# io-board-a-4.net
KiCad netlist of a schematic drawn in EAGLE
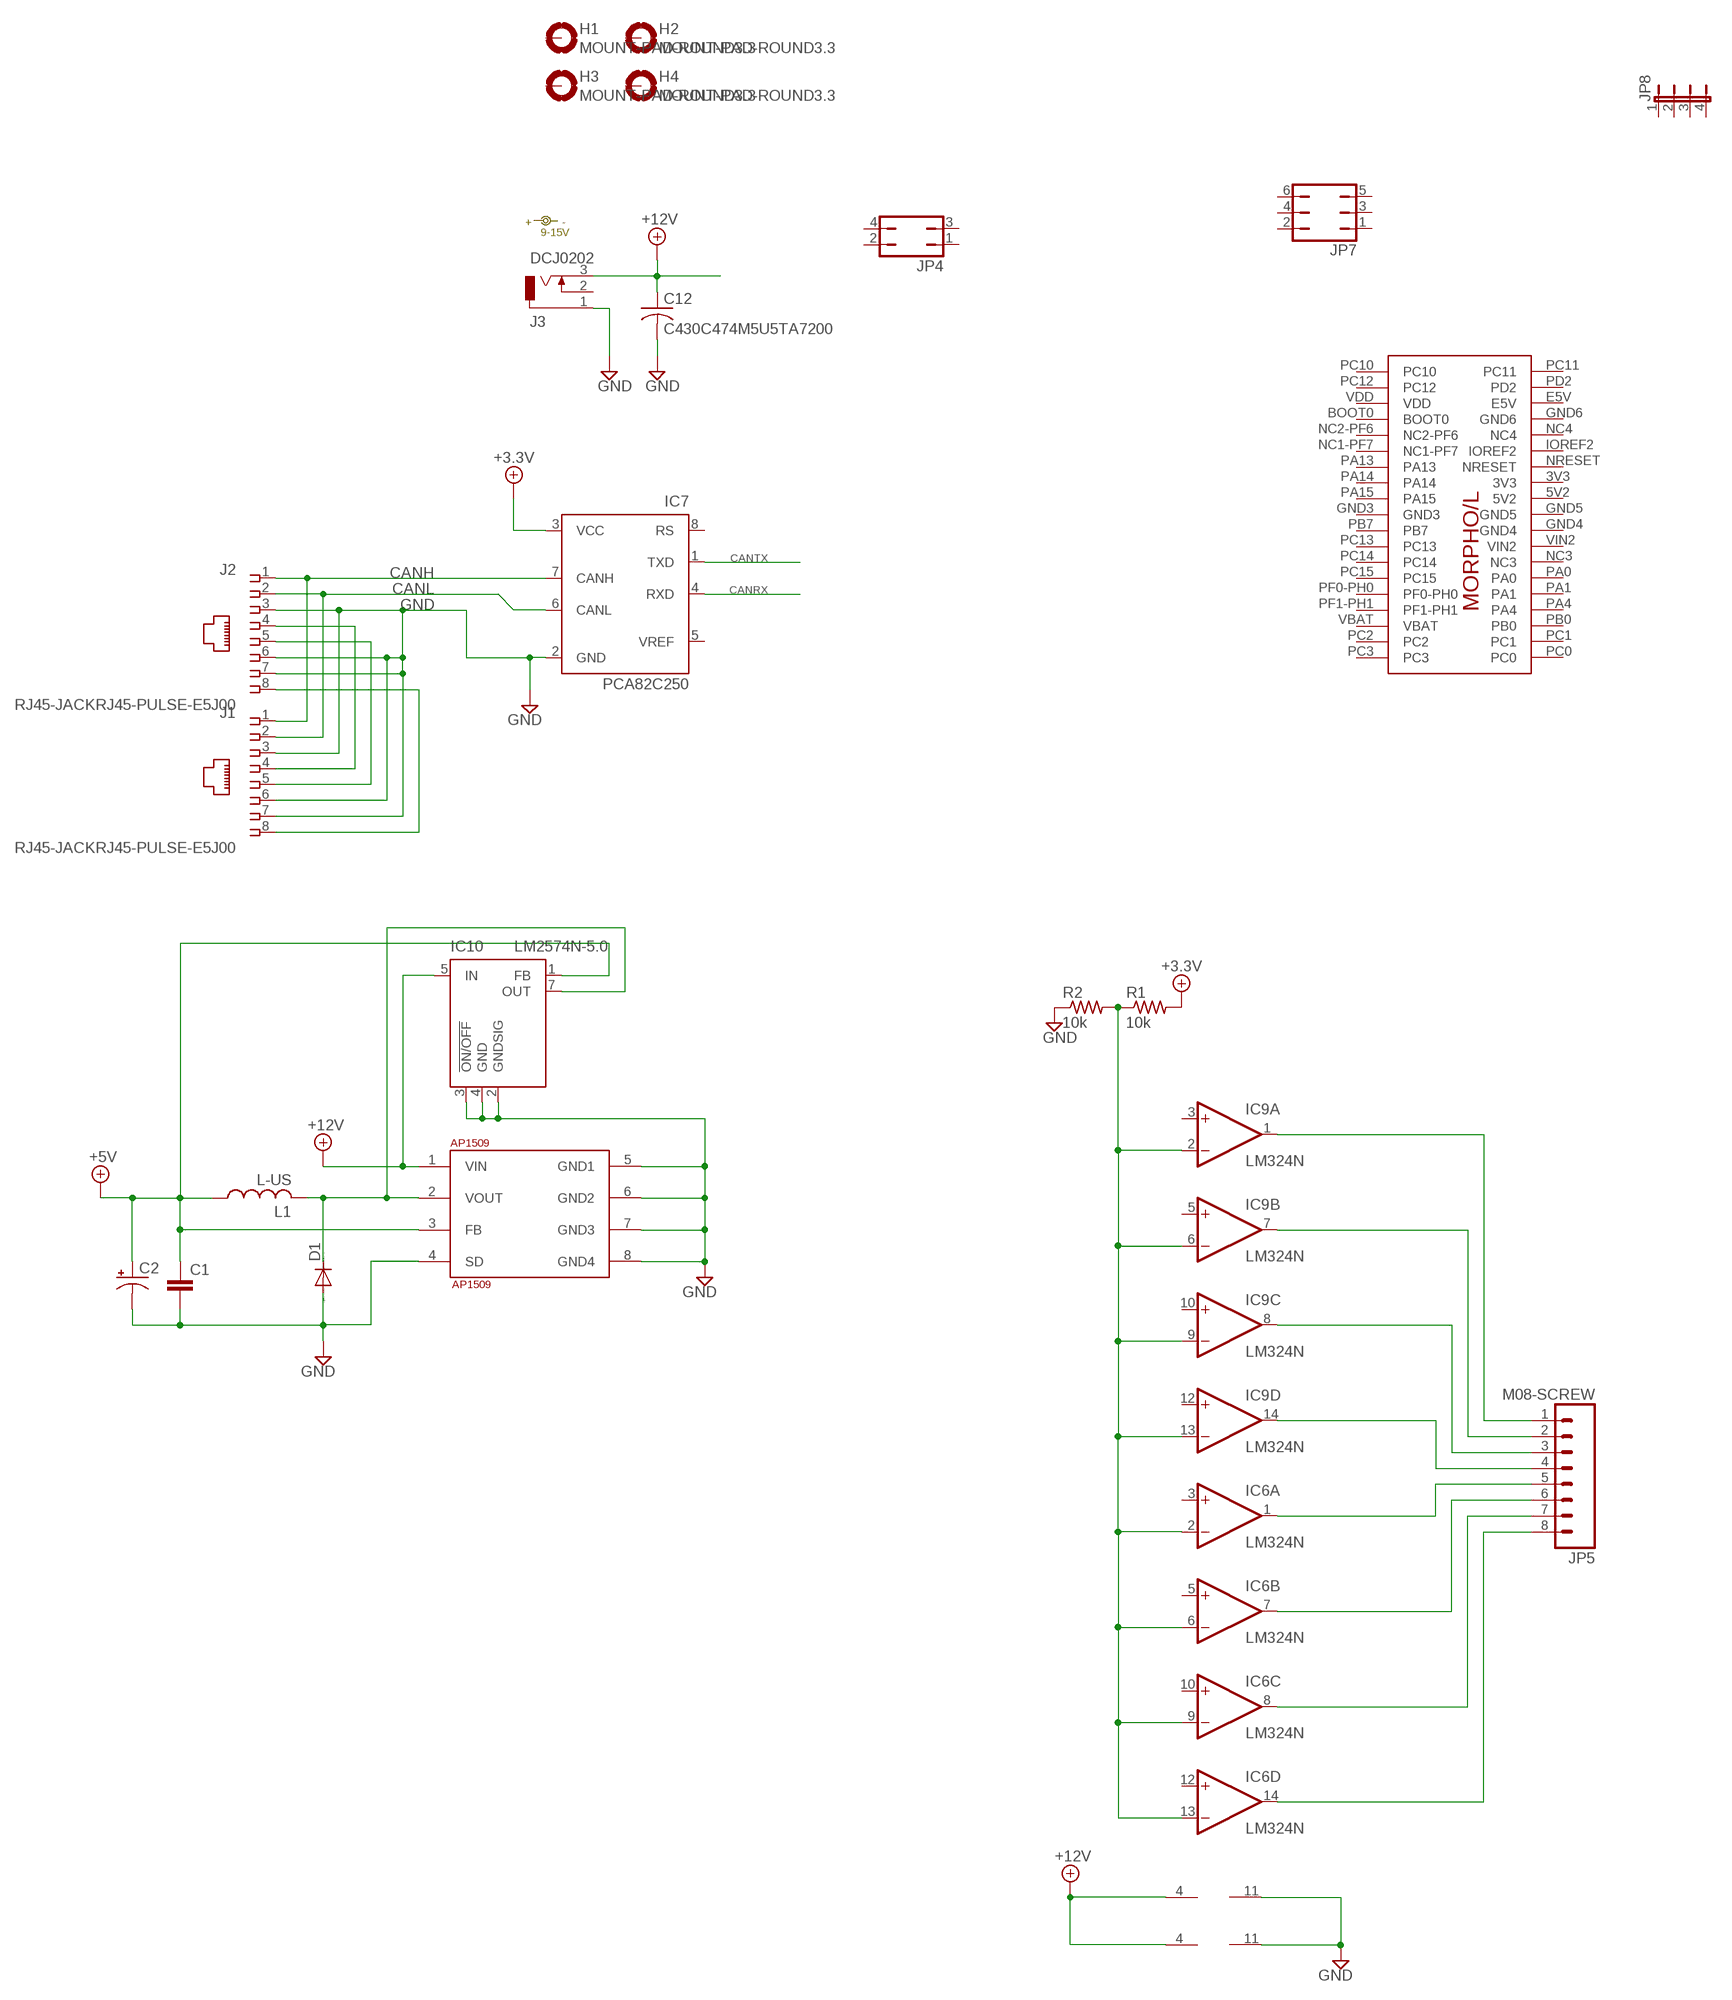
[diagram p0: schematic, sheet 1, part 1 of 2]
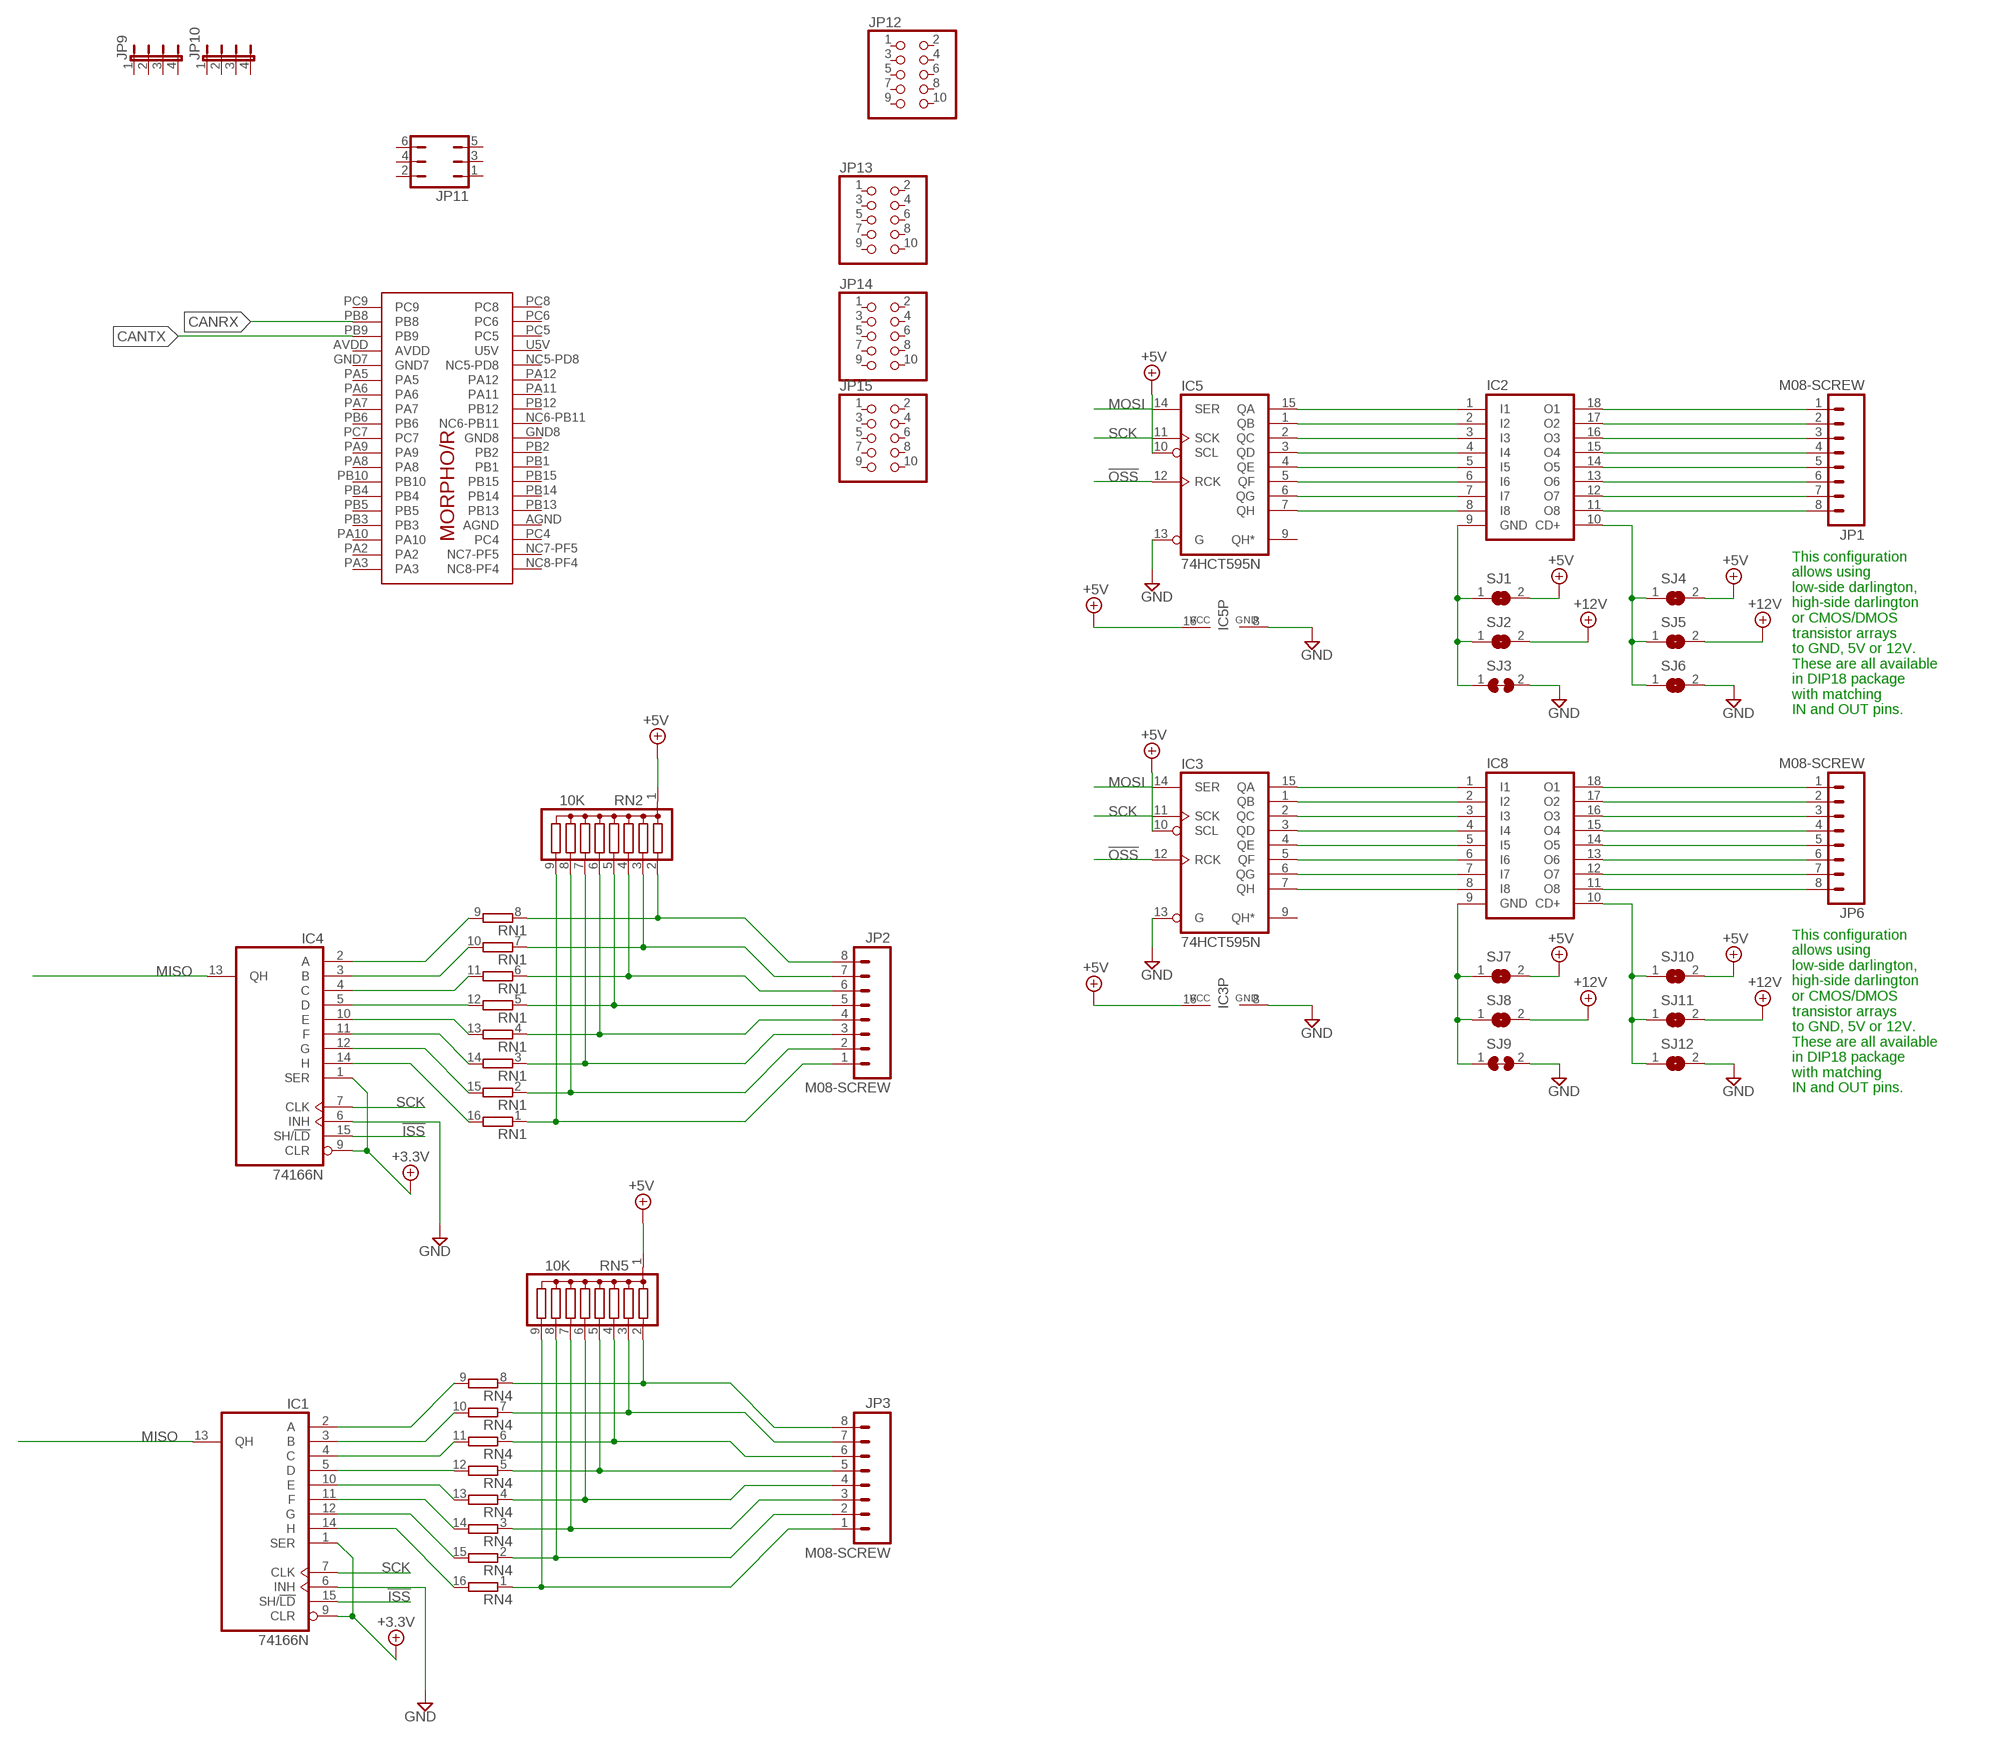
[diagram p1: schematic, sheet 1, part 2 of 2]

(export (version "E")
  (design (tool "Eeschema 10.0.6"))
  (components
    (comp (ref "+12V")
      (value "9-15V")
      (footprint "eagle-import:POWER_USAGE")
      (libsource (lib "eagle-import") (part "DOC-POWER_LABEL"))
    )
    (comp (ref "AP1509")
      (value "AP1509")
      (footprint "eagle-import:SO-08")
      (libsource (lib "eagle-import") (part "AP1509"))
    )
    (comp (ref "C1")
      (value "C-EUC1206")
      (footprint "eagle-import:C1206")
      (libsource (lib "eagle-import") (part "C-EUC1206"))
    )
    (comp (ref "C2")
      (value "CPOL-USE2.5-5")
      (footprint "eagle-import:E2,5-5")
      (libsource (lib "eagle-import") (part "CPOL-USE2.5-5"))
    )
    (comp (ref "C12")
      (value "C430C474M5U5TA7200")
      (footprint "eagle-import:C075-032X103")
      (libsource (lib "eagle-import") (part "C-US075-032X103"))
    )
    (comp (ref "D1")
      (value "DIODE-DO41-7.6")
      (footprint "eagle-import:DO41-7.6")
      (libsource (lib "eagle-import") (part "DIODE-DO41-7.6"))
    )
    (comp (ref "H1")
      (value "MOUNT-PAD-ROUND3.3")
      (footprint "eagle-import:3,3-PAD")
      (libsource (lib "eagle-import") (part "MOUNT-PAD-ROUND3.3"))
    )
    (comp (ref "H2")
      (value "MOUNT-PAD-ROUND3.3")
      (footprint "eagle-import:3,3-PAD")
      (libsource (lib "eagle-import") (part "MOUNT-PAD-ROUND3.3"))
    )
    (comp (ref "H3")
      (value "MOUNT-PAD-ROUND3.3")
      (footprint "eagle-import:3,3-PAD")
      (libsource (lib "eagle-import") (part "MOUNT-PAD-ROUND3.3"))
    )
    (comp (ref "H4")
      (value "MOUNT-PAD-ROUND3.3")
      (footprint "eagle-import:3,3-PAD")
      (libsource (lib "eagle-import") (part "MOUNT-PAD-ROUND3.3"))
    )
    (comp (ref "IC1")
      (value "74166N")
      (footprint "eagle-import:DIL16")
      (libsource (lib "eagle-import") (part "74166N"))
    )
    (comp (ref "IC2")
      (value "ULN2803A")
      (footprint "eagle-import:DIL18")
      (libsource (lib "eagle-import") (part "ULN2803A"))
    )
    (comp (ref "IC3")
      (value "74HCT595N")
      (footprint "eagle-import:DIL16")
      (libsource (lib "eagle-import") (part "74595NHCT"))
    )
    (comp (ref "IC4")
      (value "74166N")
      (footprint "eagle-import:DIL16")
      (libsource (lib "eagle-import") (part "74166N"))
    )
    (comp (ref "IC5")
      (value "74HCT595N")
      (footprint "eagle-import:DIL16")
      (libsource (lib "eagle-import") (part "74595NHCT"))
    )
    (comp (ref "IC6")
      (value "LM324N")
      (footprint "eagle-import:DIL14")
      (libsource (lib "eagle-import") (part "LM324N"))
    )
    (comp (ref "IC7")
      (value "PCA82C250")
      (footprint "eagle-import:DIL08")
      (libsource (lib "eagle-import") (part "PCA82C250"))
    )
    (comp (ref "IC8")
      (value "ULN2803A")
      (footprint "eagle-import:DIL18")
      (libsource (lib "eagle-import") (part "ULN2803A"))
    )
    (comp (ref "IC9")
      (value "LM324N")
      (footprint "eagle-import:DIL14")
      (libsource (lib "eagle-import") (part "LM324N"))
    )
    (comp (ref "IC10")
      (value "LM2574N-5.0")
      (footprint "eagle-import:DIL08")
      (libsource (lib "eagle-import") (part "LM2574?-N5.0"))
    )
    (comp (ref "J1")
      (value "RJ45-JACKRJ45-PULSE-E5J00")
      (footprint "eagle-import:RJ45-PULSE-E5J88")
      (libsource (lib "eagle-import") (part "RJ45-JACKRJ45-PULSE-E5J00"))
    )
    (comp (ref "J2")
      (value "RJ45-JACKRJ45-PULSE-E5J00")
      (footprint "eagle-import:RJ45-PULSE-E5J88")
      (libsource (lib "eagle-import") (part "RJ45-JACKRJ45-PULSE-E5J00"))
    )
    (comp (ref "J3")
      (value "DCJ0202")
      (footprint "eagle-import:DCJ0202")
      (libsource (lib "eagle-import") (part "DCJ0202"))
    )
    (comp (ref "JP1")
      (value "M08-SCREW")
      (footprint "eagle-import:1X08_TERMINAL")
      (libsource (lib "eagle-import") (part "M08-SCREW"))
    )
    (comp (ref "JP2")
      (value "M08-SCREW")
      (footprint "eagle-import:1X08_TERMINAL")
      (libsource (lib "eagle-import") (part "M08-SCREW"))
    )
    (comp (ref "JP3")
      (value "M08-SCREW")
      (footprint "eagle-import:1X08_TERMINAL")
      (libsource (lib "eagle-import") (part "M08-SCREW"))
    )
    (comp (ref "JP4")
      (value "JP2Q")
      (footprint "eagle-import:JP2Q")
      (libsource (lib "eagle-import") (part "JP2Q"))
    )
    (comp (ref "JP5")
      (value "M08-SCREW")
      (footprint "eagle-import:1X08_TERMINAL")
      (libsource (lib "eagle-import") (part "M08-SCREW"))
    )
    (comp (ref "JP6")
      (value "M08-SCREW")
      (footprint "eagle-import:1X08_TERMINAL")
      (libsource (lib "eagle-import") (part "M08-SCREW"))
    )
    (comp (ref "JP7")
      (value "JP3Q")
      (footprint "eagle-import:JP3Q")
      (libsource (lib "eagle-import") (part "JP3Q"))
    )
    (comp (ref "JP8")
      (value "JP4-FLAT")
      (footprint "eagle-import:JP4F")
      (libsource (lib "eagle-import") (part "JP4-FLAT"))
    )
    (comp (ref "JP9")
      (value "JP4-FLAT")
      (footprint "eagle-import:JP4F")
      (libsource (lib "eagle-import") (part "JP4-FLAT"))
    )
    (comp (ref "JP10")
      (value "JP4-FLAT")
      (footprint "eagle-import:JP4F")
      (libsource (lib "eagle-import") (part "JP4-FLAT"))
    )
    (comp (ref "JP11")
      (value "JP3Q")
      (footprint "eagle-import:JP3Q")
      (libsource (lib "eagle-import") (part "JP3Q"))
    )
    (comp (ref "JP12")
      (value "PINHD-2X5")
      (footprint "eagle-import:2X05")
      (libsource (lib "eagle-import") (part "PINHD-2X5"))
    )
    (comp (ref "JP13")
      (value "PINHD-2X5CN")
      (footprint "eagle-import:CON10M")
      (libsource (lib "eagle-import") (part "PINHD-2X5CN"))
    )
    (comp (ref "JP14")
      (value "PINHD-2X5CN")
      (footprint "eagle-import:CON10M")
      (libsource (lib "eagle-import") (part "PINHD-2X5CN"))
    )
    (comp (ref "JP15")
      (value "PINHD-2X5CN")
      (footprint "eagle-import:CON10M")
      (libsource (lib "eagle-import") (part "PINHD-2X5CN"))
    )
    (comp (ref "L1")
      (value "L-US")
      (footprint "eagle-import:L5-8,5")
      (libsource (lib "eagle-import") (part "L-US"))
    )
    (comp (ref "R1")
      (value "10k")
      (footprint "eagle-import:R1206")
      (libsource (lib "eagle-import") (part "R-US_R1206"))
    )
    (comp (ref "R2")
      (value "10k")
      (footprint "eagle-import:R1206")
      (libsource (lib "eagle-import") (part "R-US_R1206"))
    )
    (comp (ref "RN1")
      (value "8R-P")
      (footprint "eagle-import:DIL16")
      (libsource (lib "eagle-import") (part "8R-P"))
    )
    (comp (ref "RN2")
      (value "10K")
      (footprint "eagle-import:SIL9")
      (libsource (lib "eagle-import") (part "G08R"))
    )
    (comp (ref "RN4")
      (value "8R-P")
      (footprint "eagle-import:DIL16")
      (libsource (lib "eagle-import") (part "8R-P"))
    )
    (comp (ref "RN5")
      (value "10K")
      (footprint "eagle-import:SIL9")
      (libsource (lib "eagle-import") (part "G08R"))
    )
    (comp (ref "SJ1")
      (value "SJ")
      (footprint "eagle-import:SJ-RND")
      (libsource (lib "eagle-import") (part "SJ"))
    )
    (comp (ref "SJ2")
      (value "SJ")
      (footprint "eagle-import:SJ-RND")
      (libsource (lib "eagle-import") (part "SJ"))
    )
    (comp (ref "SJ3")
      (value "SJ-C")
      (footprint "eagle-import:SJW-C")
      (libsource (lib "eagle-import") (part "SJ-C"))
    )
    (comp (ref "SJ4")
      (value "SJ")
      (footprint "eagle-import:SJ-RND")
      (libsource (lib "eagle-import") (part "SJ"))
    )
    (comp (ref "SJ5")
      (value "SJ")
      (footprint "eagle-import:SJ-RND")
      (libsource (lib "eagle-import") (part "SJ"))
    )
    (comp (ref "SJ6")
      (value "SJ")
      (footprint "eagle-import:SJ-RND")
      (libsource (lib "eagle-import") (part "SJ"))
    )
    (comp (ref "SJ7")
      (value "SJ")
      (footprint "eagle-import:SJ-RND")
      (libsource (lib "eagle-import") (part "SJ"))
    )
    (comp (ref "SJ8")
      (value "SJ")
      (footprint "eagle-import:SJ-RND")
      (libsource (lib "eagle-import") (part "SJ"))
    )
    (comp (ref "SJ9")
      (value "SJ-C")
      (footprint "eagle-import:SJW-C")
      (libsource (lib "eagle-import") (part "SJ-C"))
    )
    (comp (ref "SJ10")
      (value "SJ")
      (footprint "eagle-import:SJ-RND")
      (libsource (lib "eagle-import") (part "SJ"))
    )
    (comp (ref "SJ11")
      (value "SJ")
      (footprint "eagle-import:SJ-RND")
      (libsource (lib "eagle-import") (part "SJ"))
    )
    (comp (ref "SJ12")
      (value "SJ")
      (footprint "eagle-import:SJ-RND")
      (libsource (lib "eagle-import") (part "SJ"))
    )
    (comp (ref "U$1")
      (value "NUCLEO_64_GENERIC")
      (footprint "eagle-import:NUCLEO_BRD_BASE64")
      (libsource (lib "eagle-import") (part "NUCLEO_64_GENERIC"))
    )
  )
  (nets
    (net (code "1") (name "+3.3V") (class "Default")
      (node (ref "IC1") (pin "1") (pinfunction "SER_1") (pintype "input"))
      (node (ref "IC1") (pin "9") (pinfunction "CLR_9") (pintype "input"))
      (node (ref "IC4") (pin "1") (pinfunction "SER_1") (pintype "input"))
      (node (ref "IC4") (pin "9") (pinfunction "CLR_9") (pintype "input"))
      (node (ref "IC7") (pin "3") (pinfunction "VCC_3") (pintype "power_in"))
      (node (ref "R1") (pin "2") (pinfunction "2_2") (pintype "passive"))
    )
    (net (code "2") (name "+5V") (class "Default")
      (node (ref "AP1509") (pin "3") (pinfunction "FB_3") (pintype "bidirectional"))
      (node (ref "C1") (pin "1") (pinfunction "1_1") (pintype "passive"))
      (node (ref "C2") (pin "+") (pinfunction "+_+") (pintype "passive"))
      (node (ref "IC10") (pin "1") (pinfunction "FB_1") (pintype "input"))
      (node (ref "IC3") (pin "10") (pinfunction "SCL_10") (pintype "input"))
      (node (ref "IC3") (pin "16") (pinfunction "VCC_16") (pintype "power_in"))
      (node (ref "IC5") (pin "10") (pinfunction "SCL_10") (pintype "input"))
      (node (ref "IC5") (pin "16") (pinfunction "VCC_16") (pintype "power_in"))
      (node (ref "L1") (pin "1") (pinfunction "1_1") (pintype "passive"))
      (node (ref "RN2") (pin "1") (pinfunction "1_1") (pintype "passive"))
      (node (ref "RN5") (pin "1") (pinfunction "1_1") (pintype "passive"))
      (node (ref "SJ1") (pin "2") (pinfunction "2_2") (pintype "passive"))
      (node (ref "SJ10") (pin "2") (pinfunction "2_2") (pintype "passive"))
      (node (ref "SJ4") (pin "2") (pinfunction "2_2") (pintype "passive"))
      (node (ref "SJ7") (pin "2") (pinfunction "2_2") (pintype "passive"))
    )
    (net (code "3") (name "+12V") (class "Default")
      (node (ref "AP1509") (pin "1") (pinfunction "VIN_1") (pintype "bidirectional"))
      (node (ref "C12") (pin "1") (pinfunction "1_1") (pintype "passive"))
      (node (ref "IC10") (pin "5") (pinfunction "IN_5") (pintype "input"))
      (node (ref "IC6") (pin "4") (pinfunction "V+_4") (pintype "power_in"))
      (node (ref "IC9") (pin "4") (pinfunction "V+_4") (pintype "power_in"))
      (node (ref "J3") (pin "3") (pinfunction "3_3") (pintype "passive"))
      (node (ref "SJ11") (pin "2") (pinfunction "2_2") (pintype "passive"))
      (node (ref "SJ2") (pin "2") (pinfunction "2_2") (pintype "passive"))
      (node (ref "SJ5") (pin "2") (pinfunction "2_2") (pintype "passive"))
      (node (ref "SJ8") (pin "2") (pinfunction "2_2") (pintype "passive"))
    )
    (net (code "4") (name "/3V3") (class "Default")
      (node (ref "U$1") (pin "3V3") (pinfunction "3V3_3V3") (pintype "power_in"))
    )
    (net (code "5") (name "/5V2") (class "Default")
      (node (ref "U$1") (pin "5V2") (pinfunction "5V2_5V2") (pintype "power_in"))
    )
    (net (code "6") (name "/AGND") (class "Default")
      (node (ref "U$1") (pin "AGND") (pinfunction "AGND_AGND") (pintype "power_in"))
    )
    (net (code "7") (name "/AVDD") (class "Default")
      (node (ref "U$1") (pin "AVDD") (pinfunction "AVDD_AVDD") (pintype "power_in"))
    )
    (net (code "8") (name "/CANH") (class "Default")
      (node (ref "IC7") (pin "7") (pinfunction "CANH_7") (pintype "bidirectional"))
      (node (ref "J1") (pin "1") (pinfunction "1_1") (pintype "passive"))
      (node (ref "J2") (pin "1") (pinfunction "1_1") (pintype "passive"))
    )
    (net (code "9") (name "/CANL") (class "Default")
      (node (ref "IC7") (pin "6") (pinfunction "CANL_6") (pintype "bidirectional"))
      (node (ref "J1") (pin "2") (pinfunction "2_2") (pintype "passive"))
      (node (ref "J2") (pin "2") (pinfunction "2_2") (pintype "passive"))
    )
    (net (code "10") (name "/E5V") (class "Default")
      (node (ref "U$1") (pin "E5V") (pinfunction "E5V_E5V") (pintype "power_in"))
    )
    (net (code "11") (name "/GND3") (class "Default")
      (node (ref "U$1") (pin "GND3") (pinfunction "GND3_GND3") (pintype "power_in"))
    )
    (net (code "12") (name "/GND4") (class "Default")
      (node (ref "U$1") (pin "GND4") (pinfunction "GND4_GND4") (pintype "power_in"))
    )
    (net (code "13") (name "/GND5") (class "Default")
      (node (ref "U$1") (pin "GND5") (pinfunction "GND5_GND5") (pintype "power_in"))
    )
    (net (code "14") (name "/GND6") (class "Default")
      (node (ref "U$1") (pin "GND6") (pinfunction "GND6_GND6") (pintype "power_in"))
    )
    (net (code "15") (name "/GND7") (class "Default")
      (node (ref "U$1") (pin "GND7") (pinfunction "GND7_GND7") (pintype "power_in"))
    )
    (net (code "16") (name "/GND8") (class "Default")
      (node (ref "U$1") (pin "GND8") (pinfunction "GND8_GND8") (pintype "power_in"))
    )
    (net (code "17") (name "/MISO") (class "Default")
      (node (ref "IC1") (pin "13") (pinfunction "QH_13") (pintype "output"))
      (node (ref "IC4") (pin "13") (pinfunction "QH_13") (pintype "output"))
    )
    (net (code "18") (name "/MOSI") (class "Default")
      (node (ref "IC3") (pin "14") (pinfunction "SER_14") (pintype "input"))
      (node (ref "IC5") (pin "14") (pinfunction "SER_14") (pintype "input"))
    )
    (net (code "19") (name "/SCK") (class "Default")
      (node (ref "IC1") (pin "7") (pinfunction "CLK_7") (pintype "input"))
      (node (ref "IC3") (pin "11") (pinfunction "SCK_11") (pintype "input"))
      (node (ref "IC4") (pin "7") (pinfunction "CLK_7") (pintype "input"))
      (node (ref "IC5") (pin "11") (pinfunction "SCK_11") (pintype "input"))
    )
    (net (code "20") (name "/U5V") (class "Default")
      (node (ref "U$1") (pin "U5V") (pinfunction "U5V_U5V") (pintype "power_in"))
    )
    (net (code "21") (name "/VBAT") (class "Default")
      (node (ref "U$1") (pin "VBAT") (pinfunction "VBAT_VBAT") (pintype "power_in"))
    )
    (net (code "22") (name "/VDD") (class "Default")
      (node (ref "U$1") (pin "VDD") (pinfunction "VDD_VDD") (pintype "power_in"))
    )
    (net (code "23") (name "/VIN2") (class "Default")
      (node (ref "U$1") (pin "VIN2") (pinfunction "VIN2_VIN2") (pintype "power_in"))
    )
    (net (code "24") (name "/~{ISS}") (class "Default")
      (node (ref "IC1") (pin "15") (pinfunction "SH/~{LD}_15") (pintype "input"))
      (node (ref "IC4") (pin "15") (pinfunction "SH/~{LD}_15") (pintype "input"))
    )
    (net (code "25") (name "/~{OSS}") (class "Default")
      (node (ref "IC3") (pin "12") (pinfunction "RCK_12") (pintype "input"))
      (node (ref "IC5") (pin "12") (pinfunction "RCK_12") (pintype "input"))
    )
    (net (code "26") (name "CANRX") (class "Default")
      (node (ref "IC7") (pin "4") (pinfunction "RXD_4") (pintype "output"))
      (node (ref "U$1") (pin "PB8") (pinfunction "PB8_PB8") (pintype "bidirectional"))
    )
    (net (code "27") (name "CANTX") (class "Default")
      (node (ref "IC7") (pin "1") (pinfunction "TXD_1") (pintype "input"))
      (node (ref "U$1") (pin "PB9") (pinfunction "PB9_PB9") (pintype "bidirectional"))
    )
    (net (code "28") (name "GND") (class "Default")
      (node (ref "AP1509") (pin "4") (pinfunction "SD_4") (pintype "bidirectional"))
      (node (ref "AP1509") (pin "5") (pinfunction "GND1_5") (pintype "power_in"))
      (node (ref "AP1509") (pin "6") (pinfunction "GND2_6") (pintype "power_in"))
      (node (ref "AP1509") (pin "7") (pinfunction "GND3_7") (pintype "power_in"))
      (node (ref "AP1509") (pin "8") (pinfunction "GND4_8") (pintype "power_in"))
      (node (ref "C1") (pin "2") (pinfunction "2_2") (pintype "passive"))
      (node (ref "C12") (pin "2") (pinfunction "2_2") (pintype "passive"))
      (node (ref "C2") (pin "-") (pinfunction "-_-") (pintype "passive"))
      (node (ref "D1") (pin "A") (pinfunction "A_A") (pintype "passive"))
      (node (ref "IC1") (pin "6") (pinfunction "INH_6") (pintype "input"))
      (node (ref "IC10") (pin "2") (pinfunction "GNDSIG_2") (pintype "input"))
      (node (ref "IC10") (pin "3") (pinfunction "~{ON/OFF}_3") (pintype "input"))
      (node (ref "IC10") (pin "4") (pinfunction "GND_4") (pintype "power_in"))
      (node (ref "IC3") (pin "13") (pinfunction "G_13") (pintype "input"))
      (node (ref "IC3") (pin "8") (pinfunction "GND_8") (pintype "power_in"))
      (node (ref "IC4") (pin "6") (pinfunction "INH_6") (pintype "input"))
      (node (ref "IC5") (pin "13") (pinfunction "G_13") (pintype "input"))
      (node (ref "IC5") (pin "8") (pinfunction "GND_8") (pintype "power_in"))
      (node (ref "IC6") (pin "11") (pinfunction "V-_11") (pintype "power_in"))
      (node (ref "IC7") (pin "2") (pinfunction "GND_2") (pintype "power_in"))
      (node (ref "IC9") (pin "11") (pinfunction "V-_11") (pintype "power_in"))
      (node (ref "J1") (pin "3") (pinfunction "3_3") (pintype "passive"))
      (node (ref "J1") (pin "6") (pinfunction "6_6") (pintype "passive"))
      (node (ref "J1") (pin "7") (pinfunction "7_7") (pintype "passive"))
      (node (ref "J2") (pin "3") (pinfunction "3_3") (pintype "passive"))
      (node (ref "J2") (pin "6") (pinfunction "6_6") (pintype "passive"))
      (node (ref "J2") (pin "7") (pinfunction "7_7") (pintype "passive"))
      (node (ref "J3") (pin "1") (pinfunction "1_1") (pintype "passive"))
      (node (ref "R2") (pin "1") (pinfunction "1_1") (pintype "passive"))
      (node (ref "SJ12") (pin "2") (pinfunction "2_2") (pintype "passive"))
      (node (ref "SJ3") (pin "2") (pinfunction "2_2") (pintype "passive"))
      (node (ref "SJ6") (pin "2") (pinfunction "2_2") (pintype "passive"))
      (node (ref "SJ9") (pin "2") (pinfunction "2_2") (pintype "passive"))
    )
    (net (code "29") (name "Net-(AP1509-VOUT)") (class "Default")
      (node (ref "AP1509") (pin "2") (pinfunction "VOUT_2") (pintype "bidirectional"))
      (node (ref "D1") (pin "C") (pinfunction "C_C") (pintype "passive"))
      (node (ref "IC10") (pin "7") (pinfunction "OUT_7") (pintype "passive"))
      (node (ref "L1") (pin "2") (pinfunction "2_2") (pintype "passive"))
    )
    (net (code "30") (name "Net-(IC1A-A)") (class "Default")
      (node (ref "IC1") (pin "2") (pinfunction "A_2") (pintype "input"))
      (node (ref "RN4") (pin "9") (pinfunction "2_9") (pintype "passive"))
    )
    (net (code "31") (name "Net-(IC1A-B)") (class "Default")
      (node (ref "IC1") (pin "3") (pinfunction "B_3") (pintype "input"))
      (node (ref "RN4") (pin "10") (pinfunction "2_10") (pintype "passive"))
    )
    (net (code "32") (name "Net-(IC1A-C)") (class "Default")
      (node (ref "IC1") (pin "4") (pinfunction "C_4") (pintype "input"))
      (node (ref "RN4") (pin "11") (pinfunction "2_11") (pintype "passive"))
    )
    (net (code "33") (name "Net-(IC1A-D)") (class "Default")
      (node (ref "IC1") (pin "5") (pinfunction "D_5") (pintype "input"))
      (node (ref "RN4") (pin "12") (pinfunction "2_12") (pintype "passive"))
    )
    (net (code "34") (name "Net-(IC1A-E)") (class "Default")
      (node (ref "IC1") (pin "10") (pinfunction "E_10") (pintype "input"))
      (node (ref "RN4") (pin "13") (pinfunction "2_13") (pintype "passive"))
    )
    (net (code "35") (name "Net-(IC1A-F)") (class "Default")
      (node (ref "IC1") (pin "11") (pinfunction "F_11") (pintype "input"))
      (node (ref "RN4") (pin "14") (pinfunction "2_14") (pintype "passive"))
    )
    (net (code "36") (name "Net-(IC1A-G)") (class "Default")
      (node (ref "IC1") (pin "12") (pinfunction "G_12") (pintype "input"))
      (node (ref "RN4") (pin "15") (pinfunction "2_15") (pintype "passive"))
    )
    (net (code "37") (name "Net-(IC1A-H)") (class "Default")
      (node (ref "IC1") (pin "14") (pinfunction "H_14") (pintype "input"))
      (node (ref "RN4") (pin "16") (pinfunction "2_16") (pintype "passive"))
    )
    (net (code "38") (name "Net-(IC2-CD+)") (class "Default")
      (node (ref "IC2") (pin "10") (pinfunction "CD+_10") (pintype "passive"))
      (node (ref "SJ4") (pin "1") (pinfunction "1_1") (pintype "passive"))
      (node (ref "SJ5") (pin "1") (pinfunction "1_1") (pintype "passive"))
      (node (ref "SJ6") (pin "1") (pinfunction "1_1") (pintype "passive"))
    )
    (net (code "39") (name "Net-(IC2-GND)") (class "Default")
      (node (ref "IC2") (pin "9") (pinfunction "GND_9") (pintype "power_in"))
      (node (ref "SJ1") (pin "1") (pinfunction "1_1") (pintype "passive"))
      (node (ref "SJ2") (pin "1") (pinfunction "1_1") (pintype "passive"))
      (node (ref "SJ3") (pin "1") (pinfunction "1_1") (pintype "passive"))
    )
    (net (code "40") (name "Net-(IC2-I1)") (class "Default")
      (node (ref "IC2") (pin "1") (pinfunction "I1_1") (pintype "input"))
      (node (ref "IC5") (pin "15") (pinfunction "QA_15") (pintype "tri_state"))
    )
    (net (code "41") (name "Net-(IC2-I2)") (class "Default")
      (node (ref "IC2") (pin "2") (pinfunction "I2_2") (pintype "input"))
      (node (ref "IC5") (pin "1") (pinfunction "QB_1") (pintype "tri_state"))
    )
    (net (code "42") (name "Net-(IC2-I3)") (class "Default")
      (node (ref "IC2") (pin "3") (pinfunction "I3_3") (pintype "input"))
      (node (ref "IC5") (pin "2") (pinfunction "QC_2") (pintype "tri_state"))
    )
    (net (code "43") (name "Net-(IC2-I4)") (class "Default")
      (node (ref "IC2") (pin "4") (pinfunction "I4_4") (pintype "input"))
      (node (ref "IC5") (pin "3") (pinfunction "QD_3") (pintype "tri_state"))
    )
    (net (code "44") (name "Net-(IC2-I5)") (class "Default")
      (node (ref "IC2") (pin "5") (pinfunction "I5_5") (pintype "input"))
      (node (ref "IC5") (pin "4") (pinfunction "QE_4") (pintype "tri_state"))
    )
    (net (code "45") (name "Net-(IC2-I6)") (class "Default")
      (node (ref "IC2") (pin "6") (pinfunction "I6_6") (pintype "input"))
      (node (ref "IC5") (pin "5") (pinfunction "QF_5") (pintype "tri_state"))
    )
    (net (code "46") (name "Net-(IC2-I7)") (class "Default")
      (node (ref "IC2") (pin "7") (pinfunction "I7_7") (pintype "input"))
      (node (ref "IC5") (pin "6") (pinfunction "QG_6") (pintype "tri_state"))
    )
    (net (code "47") (name "Net-(IC2-I8)") (class "Default")
      (node (ref "IC2") (pin "8") (pinfunction "I8_8") (pintype "input"))
      (node (ref "IC5") (pin "7") (pinfunction "QH_7") (pintype "tri_state"))
    )
    (net (code "48") (name "Net-(IC2-O1)") (class "Default")
      (node (ref "IC2") (pin "18") (pinfunction "O1_18") (pintype "open_collector"))
      (node (ref "JP1") (pin "1") (pinfunction "1_1") (pintype "passive"))
    )
    (net (code "49") (name "Net-(IC2-O2)") (class "Default")
      (node (ref "IC2") (pin "17") (pinfunction "O2_17") (pintype "open_collector"))
      (node (ref "JP1") (pin "2") (pinfunction "2_2") (pintype "passive"))
    )
    (net (code "50") (name "Net-(IC2-O3)") (class "Default")
      (node (ref "IC2") (pin "16") (pinfunction "O3_16") (pintype "open_collector"))
      (node (ref "JP1") (pin "3") (pinfunction "3_3") (pintype "passive"))
    )
    (net (code "51") (name "Net-(IC2-O4)") (class "Default")
      (node (ref "IC2") (pin "15") (pinfunction "O4_15") (pintype "open_collector"))
      (node (ref "JP1") (pin "4") (pinfunction "4_4") (pintype "passive"))
    )
    (net (code "52") (name "Net-(IC2-O5)") (class "Default")
      (node (ref "IC2") (pin "14") (pinfunction "O5_14") (pintype "open_collector"))
      (node (ref "JP1") (pin "5") (pinfunction "5_5") (pintype "passive"))
    )
    (net (code "53") (name "Net-(IC2-O6)") (class "Default")
      (node (ref "IC2") (pin "13") (pinfunction "O6_13") (pintype "open_collector"))
      (node (ref "JP1") (pin "6") (pinfunction "6_6") (pintype "passive"))
    )
    (net (code "54") (name "Net-(IC2-O7)") (class "Default")
      (node (ref "IC2") (pin "12") (pinfunction "O7_12") (pintype "open_collector"))
      (node (ref "JP1") (pin "7") (pinfunction "7_7") (pintype "passive"))
    )
    (net (code "55") (name "Net-(IC2-O8)") (class "Default")
      (node (ref "IC2") (pin "11") (pinfunction "O8_11") (pintype "open_collector"))
      (node (ref "JP1") (pin "8") (pinfunction "8_8") (pintype "passive"))
    )
    (net (code "56") (name "Net-(IC3A-QA)") (class "Default")
      (node (ref "IC3") (pin "15") (pinfunction "QA_15") (pintype "tri_state"))
      (node (ref "IC8") (pin "1") (pinfunction "I1_1") (pintype "input"))
    )
    (net (code "57") (name "Net-(IC3A-QB)") (class "Default")
      (node (ref "IC3") (pin "1") (pinfunction "QB_1") (pintype "tri_state"))
      (node (ref "IC8") (pin "2") (pinfunction "I2_2") (pintype "input"))
    )
    (net (code "58") (name "Net-(IC3A-QC)") (class "Default")
      (node (ref "IC3") (pin "2") (pinfunction "QC_2") (pintype "tri_state"))
      (node (ref "IC8") (pin "3") (pinfunction "I3_3") (pintype "input"))
    )
    (net (code "59") (name "Net-(IC3A-QD)") (class "Default")
      (node (ref "IC3") (pin "3") (pinfunction "QD_3") (pintype "tri_state"))
      (node (ref "IC8") (pin "4") (pinfunction "I4_4") (pintype "input"))
    )
    (net (code "60") (name "Net-(IC3A-QE)") (class "Default")
      (node (ref "IC3") (pin "4") (pinfunction "QE_4") (pintype "tri_state"))
      (node (ref "IC8") (pin "5") (pinfunction "I5_5") (pintype "input"))
    )
    (net (code "61") (name "Net-(IC3A-QF)") (class "Default")
      (node (ref "IC3") (pin "5") (pinfunction "QF_5") (pintype "tri_state"))
      (node (ref "IC8") (pin "6") (pinfunction "I6_6") (pintype "input"))
    )
    (net (code "62") (name "Net-(IC3A-QG)") (class "Default")
      (node (ref "IC3") (pin "6") (pinfunction "QG_6") (pintype "tri_state"))
      (node (ref "IC8") (pin "7") (pinfunction "I7_7") (pintype "input"))
    )
    (net (code "63") (name "Net-(IC3A-QH)") (class "Default")
      (node (ref "IC3") (pin "7") (pinfunction "QH_7") (pintype "tri_state"))
      (node (ref "IC8") (pin "8") (pinfunction "I8_8") (pintype "input"))
    )
    (net (code "64") (name "Net-(IC4A-A)") (class "Default")
      (node (ref "IC4") (pin "2") (pinfunction "A_2") (pintype "input"))
      (node (ref "RN1") (pin "9") (pinfunction "2_9") (pintype "passive"))
    )
    (net (code "65") (name "Net-(IC4A-B)") (class "Default")
      (node (ref "IC4") (pin "3") (pinfunction "B_3") (pintype "input"))
      (node (ref "RN1") (pin "10") (pinfunction "2_10") (pintype "passive"))
    )
    (net (code "66") (name "Net-(IC4A-C)") (class "Default")
      (node (ref "IC4") (pin "4") (pinfunction "C_4") (pintype "input"))
      (node (ref "RN1") (pin "11") (pinfunction "2_11") (pintype "passive"))
    )
    (net (code "67") (name "Net-(IC4A-D)") (class "Default")
      (node (ref "IC4") (pin "5") (pinfunction "D_5") (pintype "input"))
      (node (ref "RN1") (pin "12") (pinfunction "2_12") (pintype "passive"))
    )
    (net (code "68") (name "Net-(IC4A-E)") (class "Default")
      (node (ref "IC4") (pin "10") (pinfunction "E_10") (pintype "input"))
      (node (ref "RN1") (pin "13") (pinfunction "2_13") (pintype "passive"))
    )
    (net (code "69") (name "Net-(IC4A-F)") (class "Default")
      (node (ref "IC4") (pin "11") (pinfunction "F_11") (pintype "input"))
      (node (ref "RN1") (pin "14") (pinfunction "2_14") (pintype "passive"))
    )
    (net (code "70") (name "Net-(IC4A-G)") (class "Default")
      (node (ref "IC4") (pin "12") (pinfunction "G_12") (pintype "input"))
      (node (ref "RN1") (pin "15") (pinfunction "2_15") (pintype "passive"))
    )
    (net (code "71") (name "Net-(IC4A-H)") (class "Default")
      (node (ref "IC4") (pin "14") (pinfunction "H_14") (pintype "input"))
      (node (ref "RN1") (pin "16") (pinfunction "2_16") (pintype "passive"))
    )
    (net (code "72") (name "Net-(IC6A--IN)") (class "Default")
      (node (ref "IC6") (pin "13") (pinfunction "-IN_13") (pintype "input"))
      (node (ref "IC6") (pin "2") (pinfunction "-IN_2") (pintype "input"))
      (node (ref "IC6") (pin "6") (pinfunction "-IN_6") (pintype "input"))
      (node (ref "IC6") (pin "9") (pinfunction "-IN_9") (pintype "input"))
      (node (ref "IC9") (pin "13") (pinfunction "-IN_13") (pintype "input"))
      (node (ref "IC9") (pin "2") (pinfunction "-IN_2") (pintype "input"))
      (node (ref "IC9") (pin "6") (pinfunction "-IN_6") (pintype "input"))
      (node (ref "IC9") (pin "9") (pinfunction "-IN_9") (pintype "input"))
      (node (ref "R1") (pin "1") (pinfunction "1_1") (pintype "passive"))
      (node (ref "R2") (pin "2") (pinfunction "2_2") (pintype "passive"))
    )
    (net (code "73") (name "Net-(IC6A-OUT)") (class "Default")
      (node (ref "IC6") (pin "1") (pinfunction "OUT_1") (pintype "output"))
      (node (ref "JP5") (pin "5") (pinfunction "5_5") (pintype "passive"))
    )
    (net (code "74") (name "Net-(IC6B-OUT)") (class "Default")
      (node (ref "IC6") (pin "7") (pinfunction "OUT_7") (pintype "output"))
      (node (ref "JP5") (pin "6") (pinfunction "6_6") (pintype "passive"))
    )
    (net (code "75") (name "Net-(IC6C-OUT)") (class "Default")
      (node (ref "IC6") (pin "8") (pinfunction "OUT_8") (pintype "output"))
      (node (ref "JP5") (pin "7") (pinfunction "7_7") (pintype "passive"))
    )
    (net (code "76") (name "Net-(IC6D-OUT)") (class "Default")
      (node (ref "IC6") (pin "14") (pinfunction "OUT_14") (pintype "output"))
      (node (ref "JP5") (pin "8") (pinfunction "8_8") (pintype "passive"))
    )
    (net (code "77") (name "Net-(IC8-CD+)") (class "Default")
      (node (ref "IC8") (pin "10") (pinfunction "CD+_10") (pintype "passive"))
      (node (ref "SJ10") (pin "1") (pinfunction "1_1") (pintype "passive"))
      (node (ref "SJ11") (pin "1") (pinfunction "1_1") (pintype "passive"))
      (node (ref "SJ12") (pin "1") (pinfunction "1_1") (pintype "passive"))
    )
    (net (code "78") (name "Net-(IC8-GND)") (class "Default")
      (node (ref "IC8") (pin "9") (pinfunction "GND_9") (pintype "power_in"))
      (node (ref "SJ7") (pin "1") (pinfunction "1_1") (pintype "passive"))
      (node (ref "SJ8") (pin "1") (pinfunction "1_1") (pintype "passive"))
      (node (ref "SJ9") (pin "1") (pinfunction "1_1") (pintype "passive"))
    )
    (net (code "79") (name "Net-(IC8-O1)") (class "Default")
      (node (ref "IC8") (pin "18") (pinfunction "O1_18") (pintype "open_collector"))
      (node (ref "JP6") (pin "1") (pinfunction "1_1") (pintype "passive"))
    )
    (net (code "80") (name "Net-(IC8-O2)") (class "Default")
      (node (ref "IC8") (pin "17") (pinfunction "O2_17") (pintype "open_collector"))
      (node (ref "JP6") (pin "2") (pinfunction "2_2") (pintype "passive"))
    )
    (net (code "81") (name "Net-(IC8-O3)") (class "Default")
      (node (ref "IC8") (pin "16") (pinfunction "O3_16") (pintype "open_collector"))
      (node (ref "JP6") (pin "3") (pinfunction "3_3") (pintype "passive"))
    )
    (net (code "82") (name "Net-(IC8-O4)") (class "Default")
      (node (ref "IC8") (pin "15") (pinfunction "O4_15") (pintype "open_collector"))
      (node (ref "JP6") (pin "4") (pinfunction "4_4") (pintype "passive"))
    )
    (net (code "83") (name "Net-(IC8-O5)") (class "Default")
      (node (ref "IC8") (pin "14") (pinfunction "O5_14") (pintype "open_collector"))
      (node (ref "JP6") (pin "5") (pinfunction "5_5") (pintype "passive"))
    )
    (net (code "84") (name "Net-(IC8-O6)") (class "Default")
      (node (ref "IC8") (pin "13") (pinfunction "O6_13") (pintype "open_collector"))
      (node (ref "JP6") (pin "6") (pinfunction "6_6") (pintype "passive"))
    )
    (net (code "85") (name "Net-(IC8-O7)") (class "Default")
      (node (ref "IC8") (pin "12") (pinfunction "O7_12") (pintype "open_collector"))
      (node (ref "JP6") (pin "7") (pinfunction "7_7") (pintype "passive"))
    )
    (net (code "86") (name "Net-(IC8-O8)") (class "Default")
      (node (ref "IC8") (pin "11") (pinfunction "O8_11") (pintype "open_collector"))
      (node (ref "JP6") (pin "8") (pinfunction "8_8") (pintype "passive"))
    )
    (net (code "87") (name "Net-(IC9A-OUT)") (class "Default")
      (node (ref "IC9") (pin "1") (pinfunction "OUT_1") (pintype "output"))
      (node (ref "JP5") (pin "1") (pinfunction "1_1") (pintype "passive"))
    )
    (net (code "88") (name "Net-(IC9B-OUT)") (class "Default")
      (node (ref "IC9") (pin "7") (pinfunction "OUT_7") (pintype "output"))
      (node (ref "JP5") (pin "2") (pinfunction "2_2") (pintype "passive"))
    )
    (net (code "89") (name "Net-(IC9C-OUT)") (class "Default")
      (node (ref "IC9") (pin "8") (pinfunction "OUT_8") (pintype "output"))
      (node (ref "JP5") (pin "3") (pinfunction "3_3") (pintype "passive"))
    )
    (net (code "90") (name "Net-(IC9D-OUT)") (class "Default")
      (node (ref "IC9") (pin "14") (pinfunction "OUT_14") (pintype "output"))
      (node (ref "JP5") (pin "4") (pinfunction "4_4") (pintype "passive"))
    )
    (net (code "91") (name "Net-(J1-Pad4)") (class "Default")
      (node (ref "J1") (pin "4") (pinfunction "4_4") (pintype "passive"))
      (node (ref "J2") (pin "4") (pinfunction "4_4") (pintype "passive"))
    )
    (net (code "92") (name "Net-(J1-Pad5)") (class "Default")
      (node (ref "J1") (pin "5") (pinfunction "5_5") (pintype "passive"))
      (node (ref "J2") (pin "5") (pinfunction "5_5") (pintype "passive"))
    )
    (net (code "93") (name "Net-(J1-Pad8)") (class "Default")
      (node (ref "J1") (pin "8") (pinfunction "8_8") (pintype "passive"))
      (node (ref "J2") (pin "8") (pinfunction "8_8") (pintype "passive"))
    )
    (net (code "94") (name "Net-(JP2-Pad1)") (class "Default")
      (node (ref "JP2") (pin "1") (pinfunction "1_1") (pintype "passive"))
      (node (ref "RN1") (pin "1") (pinfunction "1_1") (pintype "passive"))
      (node (ref "RN2") (pin "9") (pinfunction "9_9") (pintype "passive"))
    )
    (net (code "95") (name "Net-(JP3-Pad1)") (class "Default")
      (node (ref "JP3") (pin "1") (pinfunction "1_1") (pintype "passive"))
      (node (ref "RN4") (pin "1") (pinfunction "1_1") (pintype "passive"))
      (node (ref "RN5") (pin "9") (pinfunction "9_9") (pintype "passive"))
    )
    (net (code "96") (name "Net-(RN1B-1)") (class "Default")
      (node (ref "JP2") (pin "2") (pinfunction "2_2") (pintype "passive"))
      (node (ref "RN1") (pin "2") (pinfunction "1_2") (pintype "passive"))
      (node (ref "RN2") (pin "8") (pinfunction "8_8") (pintype "passive"))
    )
    (net (code "97") (name "Net-(RN1C-1)") (class "Default")
      (node (ref "JP2") (pin "3") (pinfunction "3_3") (pintype "passive"))
      (node (ref "RN1") (pin "3") (pinfunction "1_3") (pintype "passive"))
      (node (ref "RN2") (pin "7") (pinfunction "7_7") (pintype "passive"))
    )
    (net (code "98") (name "Net-(RN1D-1)") (class "Default")
      (node (ref "JP2") (pin "4") (pinfunction "4_4") (pintype "passive"))
      (node (ref "RN1") (pin "4") (pinfunction "1_4") (pintype "passive"))
      (node (ref "RN2") (pin "6") (pinfunction "6_6") (pintype "passive"))
    )
    (net (code "99") (name "Net-(RN1E-1)") (class "Default")
      (node (ref "JP2") (pin "5") (pinfunction "5_5") (pintype "passive"))
      (node (ref "RN1") (pin "5") (pinfunction "1_5") (pintype "passive"))
      (node (ref "RN2") (pin "5") (pinfunction "5_5") (pintype "passive"))
    )
    (net (code "100") (name "Net-(RN1F-1)") (class "Default")
      (node (ref "JP2") (pin "6") (pinfunction "6_6") (pintype "passive"))
      (node (ref "RN1") (pin "6") (pinfunction "1_6") (pintype "passive"))
      (node (ref "RN2") (pin "4") (pinfunction "4_4") (pintype "passive"))
    )
    (net (code "101") (name "Net-(RN1G-1)") (class "Default")
      (node (ref "JP2") (pin "7") (pinfunction "7_7") (pintype "passive"))
      (node (ref "RN1") (pin "7") (pinfunction "1_7") (pintype "passive"))
      (node (ref "RN2") (pin "3") (pinfunction "3_3") (pintype "passive"))
    )
    (net (code "102") (name "Net-(RN1H-1)") (class "Default")
      (node (ref "JP2") (pin "8") (pinfunction "8_8") (pintype "passive"))
      (node (ref "RN1") (pin "8") (pinfunction "1_8") (pintype "passive"))
      (node (ref "RN2") (pin "2") (pinfunction "2_2") (pintype "passive"))
    )
    (net (code "103") (name "Net-(RN4B-1)") (class "Default")
      (node (ref "JP3") (pin "2") (pinfunction "2_2") (pintype "passive"))
      (node (ref "RN4") (pin "2") (pinfunction "1_2") (pintype "passive"))
      (node (ref "RN5") (pin "8") (pinfunction "8_8") (pintype "passive"))
    )
    (net (code "104") (name "Net-(RN4C-1)") (class "Default")
      (node (ref "JP3") (pin "3") (pinfunction "3_3") (pintype "passive"))
      (node (ref "RN4") (pin "3") (pinfunction "1_3") (pintype "passive"))
      (node (ref "RN5") (pin "7") (pinfunction "7_7") (pintype "passive"))
    )
    (net (code "105") (name "Net-(RN4D-1)") (class "Default")
      (node (ref "JP3") (pin "4") (pinfunction "4_4") (pintype "passive"))
      (node (ref "RN4") (pin "4") (pinfunction "1_4") (pintype "passive"))
      (node (ref "RN5") (pin "6") (pinfunction "6_6") (pintype "passive"))
    )
    (net (code "106") (name "Net-(RN4E-1)") (class "Default")
      (node (ref "JP3") (pin "5") (pinfunction "5_5") (pintype "passive"))
      (node (ref "RN4") (pin "5") (pinfunction "1_5") (pintype "passive"))
      (node (ref "RN5") (pin "5") (pinfunction "5_5") (pintype "passive"))
    )
    (net (code "107") (name "Net-(RN4F-1)") (class "Default")
      (node (ref "JP3") (pin "6") (pinfunction "6_6") (pintype "passive"))
      (node (ref "RN4") (pin "6") (pinfunction "1_6") (pintype "passive"))
      (node (ref "RN5") (pin "4") (pinfunction "4_4") (pintype "passive"))
    )
    (net (code "108") (name "Net-(RN4G-1)") (class "Default")
      (node (ref "JP3") (pin "7") (pinfunction "7_7") (pintype "passive"))
      (node (ref "RN4") (pin "7") (pinfunction "1_7") (pintype "passive"))
      (node (ref "RN5") (pin "3") (pinfunction "3_3") (pintype "passive"))
    )
    (net (code "109") (name "Net-(RN4H-1)") (class "Default")
      (node (ref "JP3") (pin "8") (pinfunction "8_8") (pintype "passive"))
      (node (ref "RN4") (pin "8") (pinfunction "1_8") (pintype "passive"))
      (node (ref "RN5") (pin "2") (pinfunction "2_2") (pintype "passive"))
    )
    (net (code "110") (name "unconnected-(H1-MOUNT-PadB3,3)") (class "Default")
      (node (ref "H1") (pin "B3,3") (pinfunction "MOUNT_B3,3") (pintype "passive"))
    )
    (net (code "111") (name "unconnected-(H2-MOUNT-PadB3,3)") (class "Default")
      (node (ref "H2") (pin "B3,3") (pinfunction "MOUNT_B3,3") (pintype "passive"))
    )
    (net (code "112") (name "unconnected-(H3-MOUNT-PadB3,3)") (class "Default")
      (node (ref "H3") (pin "B3,3") (pinfunction "MOUNT_B3,3") (pintype "passive"))
    )
    (net (code "113") (name "unconnected-(H4-MOUNT-PadB3,3)") (class "Default")
      (node (ref "H4") (pin "B3,3") (pinfunction "MOUNT_B3,3") (pintype "passive"))
    )
    (net (code "114") (name "unconnected-(IC3A-QH*-Pad9)") (class "Default")
      (node (ref "IC3") (pin "9") (pinfunction "QH*_9") (pintype "tri_state"))
    )
    (net (code "115") (name "unconnected-(IC5A-QH*-Pad9)") (class "Default")
      (node (ref "IC5") (pin "9") (pinfunction "QH*_9") (pintype "tri_state"))
    )
    (net (code "116") (name "unconnected-(IC6A-+IN-Pad3)") (class "Default")
      (node (ref "IC6") (pin "3") (pinfunction "+IN_3") (pintype "input"))
    )
    (net (code "117") (name "unconnected-(IC6B-+IN-Pad5)") (class "Default")
      (node (ref "IC6") (pin "5") (pinfunction "+IN_5") (pintype "input"))
    )
    (net (code "118") (name "unconnected-(IC6C-+IN-Pad10)") (class "Default")
      (node (ref "IC6") (pin "10") (pinfunction "+IN_10") (pintype "input"))
    )
    (net (code "119") (name "unconnected-(IC6D-+IN-Pad12)") (class "Default")
      (node (ref "IC6") (pin "12") (pinfunction "+IN_12") (pintype "input"))
    )
    (net (code "120") (name "unconnected-(IC7-RS-Pad8)") (class "Default")
      (node (ref "IC7") (pin "8") (pinfunction "RS_8") (pintype "input"))
    )
    (net (code "121") (name "unconnected-(IC7-VREF-Pad5)") (class "Default")
      (node (ref "IC7") (pin "5") (pinfunction "VREF_5") (pintype "output"))
    )
    (net (code "122") (name "unconnected-(IC9A-+IN-Pad3)") (class "Default")
      (node (ref "IC9") (pin "3") (pinfunction "+IN_3") (pintype "input"))
    )
    (net (code "123") (name "unconnected-(IC9B-+IN-Pad5)") (class "Default")
      (node (ref "IC9") (pin "5") (pinfunction "+IN_5") (pintype "input"))
    )
    (net (code "124") (name "unconnected-(IC9C-+IN-Pad10)") (class "Default")
      (node (ref "IC9") (pin "10") (pinfunction "+IN_10") (pintype "input"))
    )
    (net (code "125") (name "unconnected-(IC9D-+IN-Pad12)") (class "Default")
      (node (ref "IC9") (pin "12") (pinfunction "+IN_12") (pintype "input"))
    )
    (net (code "126") (name "unconnected-(J3-Pad2)") (class "Default")
      (node (ref "J3") (pin "2") (pinfunction "2_2") (pintype "passive"))
    )
    (net (code "127") (name "unconnected-(JP4-Pad1)") (class "Default")
      (node (ref "JP4") (pin "1") (pinfunction "1_1") (pintype "passive"))
    )
    (net (code "128") (name "unconnected-(JP4-Pad2)") (class "Default")
      (node (ref "JP4") (pin "2") (pinfunction "2_2") (pintype "passive"))
    )
    (net (code "129") (name "unconnected-(JP4-Pad3)") (class "Default")
      (node (ref "JP4") (pin "3") (pinfunction "3_3") (pintype "passive"))
    )
    (net (code "130") (name "unconnected-(JP4-Pad4)") (class "Default")
      (node (ref "JP4") (pin "4") (pinfunction "4_4") (pintype "passive"))
    )
    (net (code "131") (name "unconnected-(JP7-Pad1)") (class "Default")
      (node (ref "JP7") (pin "1") (pinfunction "1_1") (pintype "passive"))
    )
    (net (code "132") (name "unconnected-(JP7-Pad2)") (class "Default")
      (node (ref "JP7") (pin "2") (pinfunction "2_2") (pintype "passive"))
    )
    (net (code "133") (name "unconnected-(JP7-Pad3)") (class "Default")
      (node (ref "JP7") (pin "3") (pinfunction "3_3") (pintype "passive"))
    )
    (net (code "134") (name "unconnected-(JP7-Pad4)") (class "Default")
      (node (ref "JP7") (pin "4") (pinfunction "4_4") (pintype "passive"))
    )
    (net (code "135") (name "unconnected-(JP7-Pad5)") (class "Default")
      (node (ref "JP7") (pin "5") (pinfunction "5_5") (pintype "passive"))
    )
    (net (code "136") (name "unconnected-(JP7-Pad6)") (class "Default")
      (node (ref "JP7") (pin "6") (pinfunction "6_6") (pintype "passive"))
    )
    (net (code "137") (name "unconnected-(JP8-Pad1)") (class "Default")
      (node (ref "JP8") (pin "1") (pinfunction "1_1") (pintype "passive"))
    )
    (net (code "138") (name "unconnected-(JP8-Pad2)") (class "Default")
      (node (ref "JP8") (pin "2") (pinfunction "2_2") (pintype "passive"))
    )
    (net (code "139") (name "unconnected-(JP8-Pad3)") (class "Default")
      (node (ref "JP8") (pin "3") (pinfunction "3_3") (pintype "passive"))
    )
    (net (code "140") (name "unconnected-(JP8-Pad4)") (class "Default")
      (node (ref "JP8") (pin "4") (pinfunction "4_4") (pintype "passive"))
    )
    (net (code "141") (name "unconnected-(JP9-Pad1)") (class "Default")
      (node (ref "JP9") (pin "1") (pinfunction "1_1") (pintype "passive"))
    )
    (net (code "142") (name "unconnected-(JP9-Pad2)") (class "Default")
      (node (ref "JP9") (pin "2") (pinfunction "2_2") (pintype "passive"))
    )
    (net (code "143") (name "unconnected-(JP9-Pad3)") (class "Default")
      (node (ref "JP9") (pin "3") (pinfunction "3_3") (pintype "passive"))
    )
    (net (code "144") (name "unconnected-(JP9-Pad4)") (class "Default")
      (node (ref "JP9") (pin "4") (pinfunction "4_4") (pintype "passive"))
    )
    (net (code "145") (name "unconnected-(JP10-Pad1)") (class "Default")
      (node (ref "JP10") (pin "1") (pinfunction "1_1") (pintype "passive"))
    )
    (net (code "146") (name "unconnected-(JP10-Pad2)") (class "Default")
      (node (ref "JP10") (pin "2") (pinfunction "2_2") (pintype "passive"))
    )
    (net (code "147") (name "unconnected-(JP10-Pad3)") (class "Default")
      (node (ref "JP10") (pin "3") (pinfunction "3_3") (pintype "passive"))
    )
    (net (code "148") (name "unconnected-(JP10-Pad4)") (class "Default")
      (node (ref "JP10") (pin "4") (pinfunction "4_4") (pintype "passive"))
    )
    (net (code "149") (name "unconnected-(JP11-Pad1)") (class "Default")
      (node (ref "JP11") (pin "1") (pinfunction "1_1") (pintype "passive"))
    )
    (net (code "150") (name "unconnected-(JP11-Pad2)") (class "Default")
      (node (ref "JP11") (pin "2") (pinfunction "2_2") (pintype "passive"))
    )
    (net (code "151") (name "unconnected-(JP11-Pad3)") (class "Default")
      (node (ref "JP11") (pin "3") (pinfunction "3_3") (pintype "passive"))
    )
    (net (code "152") (name "unconnected-(JP11-Pad4)") (class "Default")
      (node (ref "JP11") (pin "4") (pinfunction "4_4") (pintype "passive"))
    )
    (net (code "153") (name "unconnected-(JP11-Pad5)") (class "Default")
      (node (ref "JP11") (pin "5") (pinfunction "5_5") (pintype "passive"))
    )
    (net (code "154") (name "unconnected-(JP11-Pad6)") (class "Default")
      (node (ref "JP11") (pin "6") (pinfunction "6_6") (pintype "passive"))
    )
    (net (code "155") (name "unconnected-(JP12-Pad1)") (class "Default")
      (node (ref "JP12") (pin "1") (pinfunction "1_1") (pintype "passive"))
    )
    (net (code "156") (name "unconnected-(JP12-Pad2)") (class "Default")
      (node (ref "JP12") (pin "2") (pinfunction "2_2") (pintype "passive"))
    )
    (net (code "157") (name "unconnected-(JP12-Pad3)") (class "Default")
      (node (ref "JP12") (pin "3") (pinfunction "3_3") (pintype "passive"))
    )
    (net (code "158") (name "unconnected-(JP12-Pad4)") (class "Default")
      (node (ref "JP12") (pin "4") (pinfunction "4_4") (pintype "passive"))
    )
    (net (code "159") (name "unconnected-(JP12-Pad5)") (class "Default")
      (node (ref "JP12") (pin "5") (pinfunction "5_5") (pintype "passive"))
    )
    (net (code "160") (name "unconnected-(JP12-Pad6)") (class "Default")
      (node (ref "JP12") (pin "6") (pinfunction "6_6") (pintype "passive"))
    )
    (net (code "161") (name "unconnected-(JP12-Pad7)") (class "Default")
      (node (ref "JP12") (pin "7") (pinfunction "7_7") (pintype "passive"))
    )
    (net (code "162") (name "unconnected-(JP12-Pad8)") (class "Default")
      (node (ref "JP12") (pin "8") (pinfunction "8_8") (pintype "passive"))
    )
    (net (code "163") (name "unconnected-(JP12-Pad9)") (class "Default")
      (node (ref "JP12") (pin "9") (pinfunction "9_9") (pintype "passive"))
    )
    (net (code "164") (name "unconnected-(JP12-Pad10)") (class "Default")
      (node (ref "JP12") (pin "10") (pinfunction "10_10") (pintype "passive"))
    )
    (net (code "165") (name "unconnected-(JP13-Pad1)") (class "Default")
      (node (ref "JP13") (pin "1") (pinfunction "1_1") (pintype "passive"))
    )
    (net (code "166") (name "unconnected-(JP13-Pad2)") (class "Default")
      (node (ref "JP13") (pin "2") (pinfunction "2_2") (pintype "passive"))
    )
    (net (code "167") (name "unconnected-(JP13-Pad3)") (class "Default")
      (node (ref "JP13") (pin "3") (pinfunction "3_3") (pintype "passive"))
    )
    (net (code "168") (name "unconnected-(JP13-Pad4)") (class "Default")
      (node (ref "JP13") (pin "4") (pinfunction "4_4") (pintype "passive"))
    )
    (net (code "169") (name "unconnected-(JP13-Pad5)") (class "Default")
      (node (ref "JP13") (pin "5") (pinfunction "5_5") (pintype "passive"))
    )
    (net (code "170") (name "unconnected-(JP13-Pad6)") (class "Default")
      (node (ref "JP13") (pin "6") (pinfunction "6_6") (pintype "passive"))
    )
    (net (code "171") (name "unconnected-(JP13-Pad7)") (class "Default")
      (node (ref "JP13") (pin "7") (pinfunction "7_7") (pintype "passive"))
    )
    (net (code "172") (name "unconnected-(JP13-Pad8)") (class "Default")
      (node (ref "JP13") (pin "8") (pinfunction "8_8") (pintype "passive"))
    )
    (net (code "173") (name "unconnected-(JP13-Pad9)") (class "Default")
      (node (ref "JP13") (pin "9") (pinfunction "9_9") (pintype "passive"))
    )
    (net (code "174") (name "unconnected-(JP13-Pad10)") (class "Default")
      (node (ref "JP13") (pin "10") (pinfunction "10_10") (pintype "passive"))
    )
    (net (code "175") (name "unconnected-(JP14-Pad1)") (class "Default")
      (node (ref "JP14") (pin "1") (pinfunction "1_1") (pintype "passive"))
    )
    (net (code "176") (name "unconnected-(JP14-Pad2)") (class "Default")
      (node (ref "JP14") (pin "2") (pinfunction "2_2") (pintype "passive"))
    )
    (net (code "177") (name "unconnected-(JP14-Pad3)") (class "Default")
      (node (ref "JP14") (pin "3") (pinfunction "3_3") (pintype "passive"))
    )
    (net (code "178") (name "unconnected-(JP14-Pad4)") (class "Default")
      (node (ref "JP14") (pin "4") (pinfunction "4_4") (pintype "passive"))
    )
    (net (code "179") (name "unconnected-(JP14-Pad5)") (class "Default")
      (node (ref "JP14") (pin "5") (pinfunction "5_5") (pintype "passive"))
    )
    (net (code "180") (name "unconnected-(JP14-Pad6)") (class "Default")
      (node (ref "JP14") (pin "6") (pinfunction "6_6") (pintype "passive"))
    )
    (net (code "181") (name "unconnected-(JP14-Pad7)") (class "Default")
      (node (ref "JP14") (pin "7") (pinfunction "7_7") (pintype "passive"))
    )
    (net (code "182") (name "unconnected-(JP14-Pad8)") (class "Default")
      (node (ref "JP14") (pin "8") (pinfunction "8_8") (pintype "passive"))
    )
    (net (code "183") (name "unconnected-(JP14-Pad9)") (class "Default")
      (node (ref "JP14") (pin "9") (pinfunction "9_9") (pintype "passive"))
    )
    (net (code "184") (name "unconnected-(JP14-Pad10)") (class "Default")
      (node (ref "JP14") (pin "10") (pinfunction "10_10") (pintype "passive"))
    )
    (net (code "185") (name "unconnected-(JP15-Pad1)") (class "Default")
      (node (ref "JP15") (pin "1") (pinfunction "1_1") (pintype "passive"))
    )
    (net (code "186") (name "unconnected-(JP15-Pad2)") (class "Default")
      (node (ref "JP15") (pin "2") (pinfunction "2_2") (pintype "passive"))
    )
    (net (code "187") (name "unconnected-(JP15-Pad3)") (class "Default")
      (node (ref "JP15") (pin "3") (pinfunction "3_3") (pintype "passive"))
    )
    (net (code "188") (name "unconnected-(JP15-Pad4)") (class "Default")
      (node (ref "JP15") (pin "4") (pinfunction "4_4") (pintype "passive"))
    )
    (net (code "189") (name "unconnected-(JP15-Pad5)") (class "Default")
      (node (ref "JP15") (pin "5") (pinfunction "5_5") (pintype "passive"))
    )
    (net (code "190") (name "unconnected-(JP15-Pad6)") (class "Default")
      (node (ref "JP15") (pin "6") (pinfunction "6_6") (pintype "passive"))
    )
    (net (code "191") (name "unconnected-(JP15-Pad7)") (class "Default")
      (node (ref "JP15") (pin "7") (pinfunction "7_7") (pintype "passive"))
    )
    (net (code "192") (name "unconnected-(JP15-Pad8)") (class "Default")
      (node (ref "JP15") (pin "8") (pinfunction "8_8") (pintype "passive"))
    )
    (net (code "193") (name "unconnected-(JP15-Pad9)") (class "Default")
      (node (ref "JP15") (pin "9") (pinfunction "9_9") (pintype "passive"))
    )
    (net (code "194") (name "unconnected-(JP15-Pad10)") (class "Default")
      (node (ref "JP15") (pin "10") (pinfunction "10_10") (pintype "passive"))
    )
    (net (code "195") (name "unconnected-(U$1-PadBOOT0)") (class "Default")
      (node (ref "U$1") (pin "BOOT0") (pinfunction "BOOT0_BOOT0") (pintype "bidirectional"))
    )
    (net (code "196") (name "unconnected-(U$1-PadIOREF2)") (class "Default")
      (node (ref "U$1") (pin "IOREF2") (pinfunction "IOREF2_IOREF2") (pintype "input"))
    )
    (net (code "197") (name "unconnected-(U$1-PadNC1-PF7)") (class "Default")
      (node (ref "U$1") (pin "NC1-PF7") (pinfunction "NC1-PF7_NC1-PF7") (pintype "bidirectional"))
    )
    (net (code "198") (name "unconnected-(U$1-PadNC2-PF6)") (class "Default")
      (node (ref "U$1") (pin "NC2-PF6") (pinfunction "NC2-PF6_NC2-PF6") (pintype "bidirectional"))
    )
    (net (code "199") (name "unconnected-(U$1-PadNC3)") (class "Default")
      (node (ref "U$1") (pin "NC3") (pinfunction "NC3_NC3") (pintype "no_connect"))
    )
    (net (code "200") (name "unconnected-(U$1-PadNC4)") (class "Default")
      (node (ref "U$1") (pin "NC4") (pinfunction "NC4_NC4") (pintype "no_connect"))
    )
    (net (code "201") (name "unconnected-(U$1-PadNC5-PD8)") (class "Default")
      (node (ref "U$1") (pin "NC5-PD8") (pinfunction "NC5-PD8_NC5-PD8") (pintype "bidirectional"))
    )
    (net (code "202") (name "unconnected-(U$1-PadNC6-PB11)") (class "Default")
      (node (ref "U$1") (pin "NC6-PB11") (pinfunction "NC6-PB11_NC6-PB11") (pintype "no_connect"))
    )
    (net (code "203") (name "unconnected-(U$1-PadNC7-PF5)") (class "Default")
      (node (ref "U$1") (pin "NC7-PF5") (pinfunction "NC7-PF5_NC7-PF5") (pintype "bidirectional"))
    )
    (net (code "204") (name "unconnected-(U$1-PadNC8-PF4)") (class "Default")
      (node (ref "U$1") (pin "NC8-PF4") (pinfunction "NC8-PF4_NC8-PF4") (pintype "bidirectional"))
    )
    (net (code "205") (name "unconnected-(U$1-PadNRESET)") (class "Default")
      (node (ref "U$1") (pin "NRESET") (pinfunction "NRESET_NRESET") (pintype "input"))
    )
    (net (code "206") (name "unconnected-(U$1-PadPA0)") (class "Default")
      (node (ref "U$1") (pin "PA0") (pinfunction "PA0_PA0") (pintype "bidirectional"))
    )
    (net (code "207") (name "unconnected-(U$1-PadPA1)") (class "Default")
      (node (ref "U$1") (pin "PA1") (pinfunction "PA1_PA1") (pintype "bidirectional"))
    )
    (net (code "208") (name "unconnected-(U$1-PadPA2)") (class "Default")
      (node (ref "U$1") (pin "PA2") (pinfunction "PA2_PA2") (pintype "bidirectional"))
    )
    (net (code "209") (name "unconnected-(U$1-PadPA3)") (class "Default")
      (node (ref "U$1") (pin "PA3") (pinfunction "PA3_PA3") (pintype "bidirectional"))
    )
    (net (code "210") (name "unconnected-(U$1-PadPA4)") (class "Default")
      (node (ref "U$1") (pin "PA4") (pinfunction "PA4_PA4") (pintype "bidirectional"))
    )
    (net (code "211") (name "unconnected-(U$1-PadPA5)") (class "Default")
      (node (ref "U$1") (pin "PA5") (pinfunction "PA5_PA5") (pintype "bidirectional"))
    )
    (net (code "212") (name "unconnected-(U$1-PadPA6)") (class "Default")
      (node (ref "U$1") (pin "PA6") (pinfunction "PA6_PA6") (pintype "bidirectional"))
    )
    (net (code "213") (name "unconnected-(U$1-PadPA7)") (class "Default")
      (node (ref "U$1") (pin "PA7") (pinfunction "PA7_PA7") (pintype "bidirectional"))
    )
    (net (code "214") (name "unconnected-(U$1-PadPA8)") (class "Default")
      (node (ref "U$1") (pin "PA8") (pinfunction "PA8_PA8") (pintype "bidirectional"))
    )
    (net (code "215") (name "unconnected-(U$1-PadPA9)") (class "Default")
      (node (ref "U$1") (pin "PA9") (pinfunction "PA9_PA9") (pintype "bidirectional"))
    )
    (net (code "216") (name "unconnected-(U$1-PadPA10)") (class "Default")
      (node (ref "U$1") (pin "PA10") (pinfunction "PA10_PA10") (pintype "bidirectional"))
    )
    (net (code "217") (name "unconnected-(U$1-PadPA11)") (class "Default")
      (node (ref "U$1") (pin "PA11") (pinfunction "PA11_PA11") (pintype "bidirectional"))
    )
    (net (code "218") (name "unconnected-(U$1-PadPA12)") (class "Default")
      (node (ref "U$1") (pin "PA12") (pinfunction "PA12_PA12") (pintype "bidirectional"))
    )
    (net (code "219") (name "unconnected-(U$1-PadPA13)") (class "Default")
      (node (ref "U$1") (pin "PA13") (pinfunction "PA13_PA13") (pintype "bidirectional"))
    )
    (net (code "220") (name "unconnected-(U$1-PadPA14)") (class "Default")
      (node (ref "U$1") (pin "PA14") (pinfunction "PA14_PA14") (pintype "bidirectional"))
    )
    (net (code "221") (name "unconnected-(U$1-PadPA15)") (class "Default")
      (node (ref "U$1") (pin "PA15") (pinfunction "PA15_PA15") (pintype "bidirectional"))
    )
    (net (code "222") (name "unconnected-(U$1-PadPB0)") (class "Default")
      (node (ref "U$1") (pin "PB0") (pinfunction "PB0_PB0") (pintype "bidirectional"))
    )
    (net (code "223") (name "unconnected-(U$1-PadPB1)") (class "Default")
      (node (ref "U$1") (pin "PB1") (pinfunction "PB1_PB1") (pintype "bidirectional"))
    )
    (net (code "224") (name "unconnected-(U$1-PadPB2)") (class "Default")
      (node (ref "U$1") (pin "PB2") (pinfunction "PB2_PB2") (pintype "bidirectional"))
    )
    (net (code "225") (name "unconnected-(U$1-PadPB3)") (class "Default")
      (node (ref "U$1") (pin "PB3") (pinfunction "PB3_PB3") (pintype "bidirectional"))
    )
    (net (code "226") (name "unconnected-(U$1-PadPB4)") (class "Default")
      (node (ref "U$1") (pin "PB4") (pinfunction "PB4_PB4") (pintype "bidirectional"))
    )
    (net (code "227") (name "unconnected-(U$1-PadPB5)") (class "Default")
      (node (ref "U$1") (pin "PB5") (pinfunction "PB5_PB5") (pintype "bidirectional"))
    )
    (net (code "228") (name "unconnected-(U$1-PadPB6)") (class "Default")
      (node (ref "U$1") (pin "PB6") (pinfunction "PB6_PB6") (pintype "bidirectional"))
    )
    (net (code "229") (name "unconnected-(U$1-PadPB7)") (class "Default")
      (node (ref "U$1") (pin "PB7") (pinfunction "PB7_PB7") (pintype "bidirectional"))
    )
    (net (code "230") (name "unconnected-(U$1-PadPB10)") (class "Default")
      (node (ref "U$1") (pin "PB10") (pinfunction "PB10_PB10") (pintype "bidirectional"))
    )
    (net (code "231") (name "unconnected-(U$1-PadPB12)") (class "Default")
      (node (ref "U$1") (pin "PB12") (pinfunction "PB12_PB12") (pintype "bidirectional"))
    )
    (net (code "232") (name "unconnected-(U$1-PadPB13)") (class "Default")
      (node (ref "U$1") (pin "PB13") (pinfunction "PB13_PB13") (pintype "bidirectional"))
    )
    (net (code "233") (name "unconnected-(U$1-PadPB14)") (class "Default")
      (node (ref "U$1") (pin "PB14") (pinfunction "PB14_PB14") (pintype "bidirectional"))
    )
    (net (code "234") (name "unconnected-(U$1-PadPB15)") (class "Default")
      (node (ref "U$1") (pin "PB15") (pinfunction "PB15_PB15") (pintype "bidirectional"))
    )
    (net (code "235") (name "unconnected-(U$1-PadPC0)") (class "Default")
      (node (ref "U$1") (pin "PC0") (pinfunction "PC0_PC0") (pintype "bidirectional"))
    )
    (net (code "236") (name "unconnected-(U$1-PadPC1)") (class "Default")
      (node (ref "U$1") (pin "PC1") (pinfunction "PC1_PC1") (pintype "bidirectional"))
    )
    (net (code "237") (name "unconnected-(U$1-PadPC2)") (class "Default")
      (node (ref "U$1") (pin "PC2") (pinfunction "PC2_PC2") (pintype "bidirectional"))
    )
    (net (code "238") (name "unconnected-(U$1-PadPC3)") (class "Default")
      (node (ref "U$1") (pin "PC3") (pinfunction "PC3_PC3") (pintype "bidirectional"))
    )
    (net (code "239") (name "unconnected-(U$1-PadPC4)") (class "Default")
      (node (ref "U$1") (pin "PC4") (pinfunction "PC4_PC4") (pintype "bidirectional"))
    )
    (net (code "240") (name "unconnected-(U$1-PadPC5)") (class "Default")
      (node (ref "U$1") (pin "PC5") (pinfunction "PC5_PC5") (pintype "bidirectional"))
    )
    (net (code "241") (name "unconnected-(U$1-PadPC6)") (class "Default")
      (node (ref "U$1") (pin "PC6") (pinfunction "PC6_PC6") (pintype "bidirectional"))
    )
    (net (code "242") (name "unconnected-(U$1-PadPC7)") (class "Default")
      (node (ref "U$1") (pin "PC7") (pinfunction "PC7_PC7") (pintype "bidirectional"))
    )
    (net (code "243") (name "unconnected-(U$1-PadPC8)") (class "Default")
      (node (ref "U$1") (pin "PC8") (pinfunction "PC8_PC8") (pintype "bidirectional"))
    )
    (net (code "244") (name "unconnected-(U$1-PadPC9)") (class "Default")
      (node (ref "U$1") (pin "PC9") (pinfunction "PC9_PC9") (pintype "bidirectional"))
    )
    (net (code "245") (name "unconnected-(U$1-PadPC10)") (class "Default")
      (node (ref "U$1") (pin "PC10") (pinfunction "PC10_PC10") (pintype "bidirectional"))
    )
    (net (code "246") (name "unconnected-(U$1-PadPC11)") (class "Default")
      (node (ref "U$1") (pin "PC11") (pinfunction "PC11_PC11") (pintype "bidirectional"))
    )
    (net (code "247") (name "unconnected-(U$1-PadPC12)") (class "Default")
      (node (ref "U$1") (pin "PC12") (pinfunction "PC12_PC12") (pintype "bidirectional"))
    )
    (net (code "248") (name "unconnected-(U$1-PadPC13)") (class "Default")
      (node (ref "U$1") (pin "PC13") (pinfunction "PC13_PC13") (pintype "bidirectional"))
    )
    (net (code "249") (name "unconnected-(U$1-PadPC14)") (class "Default")
      (node (ref "U$1") (pin "PC14") (pinfunction "PC14_PC14") (pintype "bidirectional"))
    )
    (net (code "250") (name "unconnected-(U$1-PadPC15)") (class "Default")
      (node (ref "U$1") (pin "PC15") (pinfunction "PC15_PC15") (pintype "bidirectional"))
    )
    (net (code "251") (name "unconnected-(U$1-PadPD2)") (class "Default")
      (node (ref "U$1") (pin "PD2") (pinfunction "PD2_PD2") (pintype "bidirectional"))
    )
    (net (code "252") (name "unconnected-(U$1-PadPF0-PH0)") (class "Default")
      (node (ref "U$1") (pin "PF0-PH0") (pinfunction "PF0-PH0_PF0-PH0") (pintype "bidirectional"))
    )
    (net (code "253") (name "unconnected-(U$1-PadPF1-PH1)") (class "Default")
      (node (ref "U$1") (pin "PF1-PH1") (pinfunction "PF1-PH1_PF1-PH1") (pintype "bidirectional"))
    )
  )
)
